# TSL45315-Breakout_v11.net
KiCad netlist of a schematic drawn in EAGLE
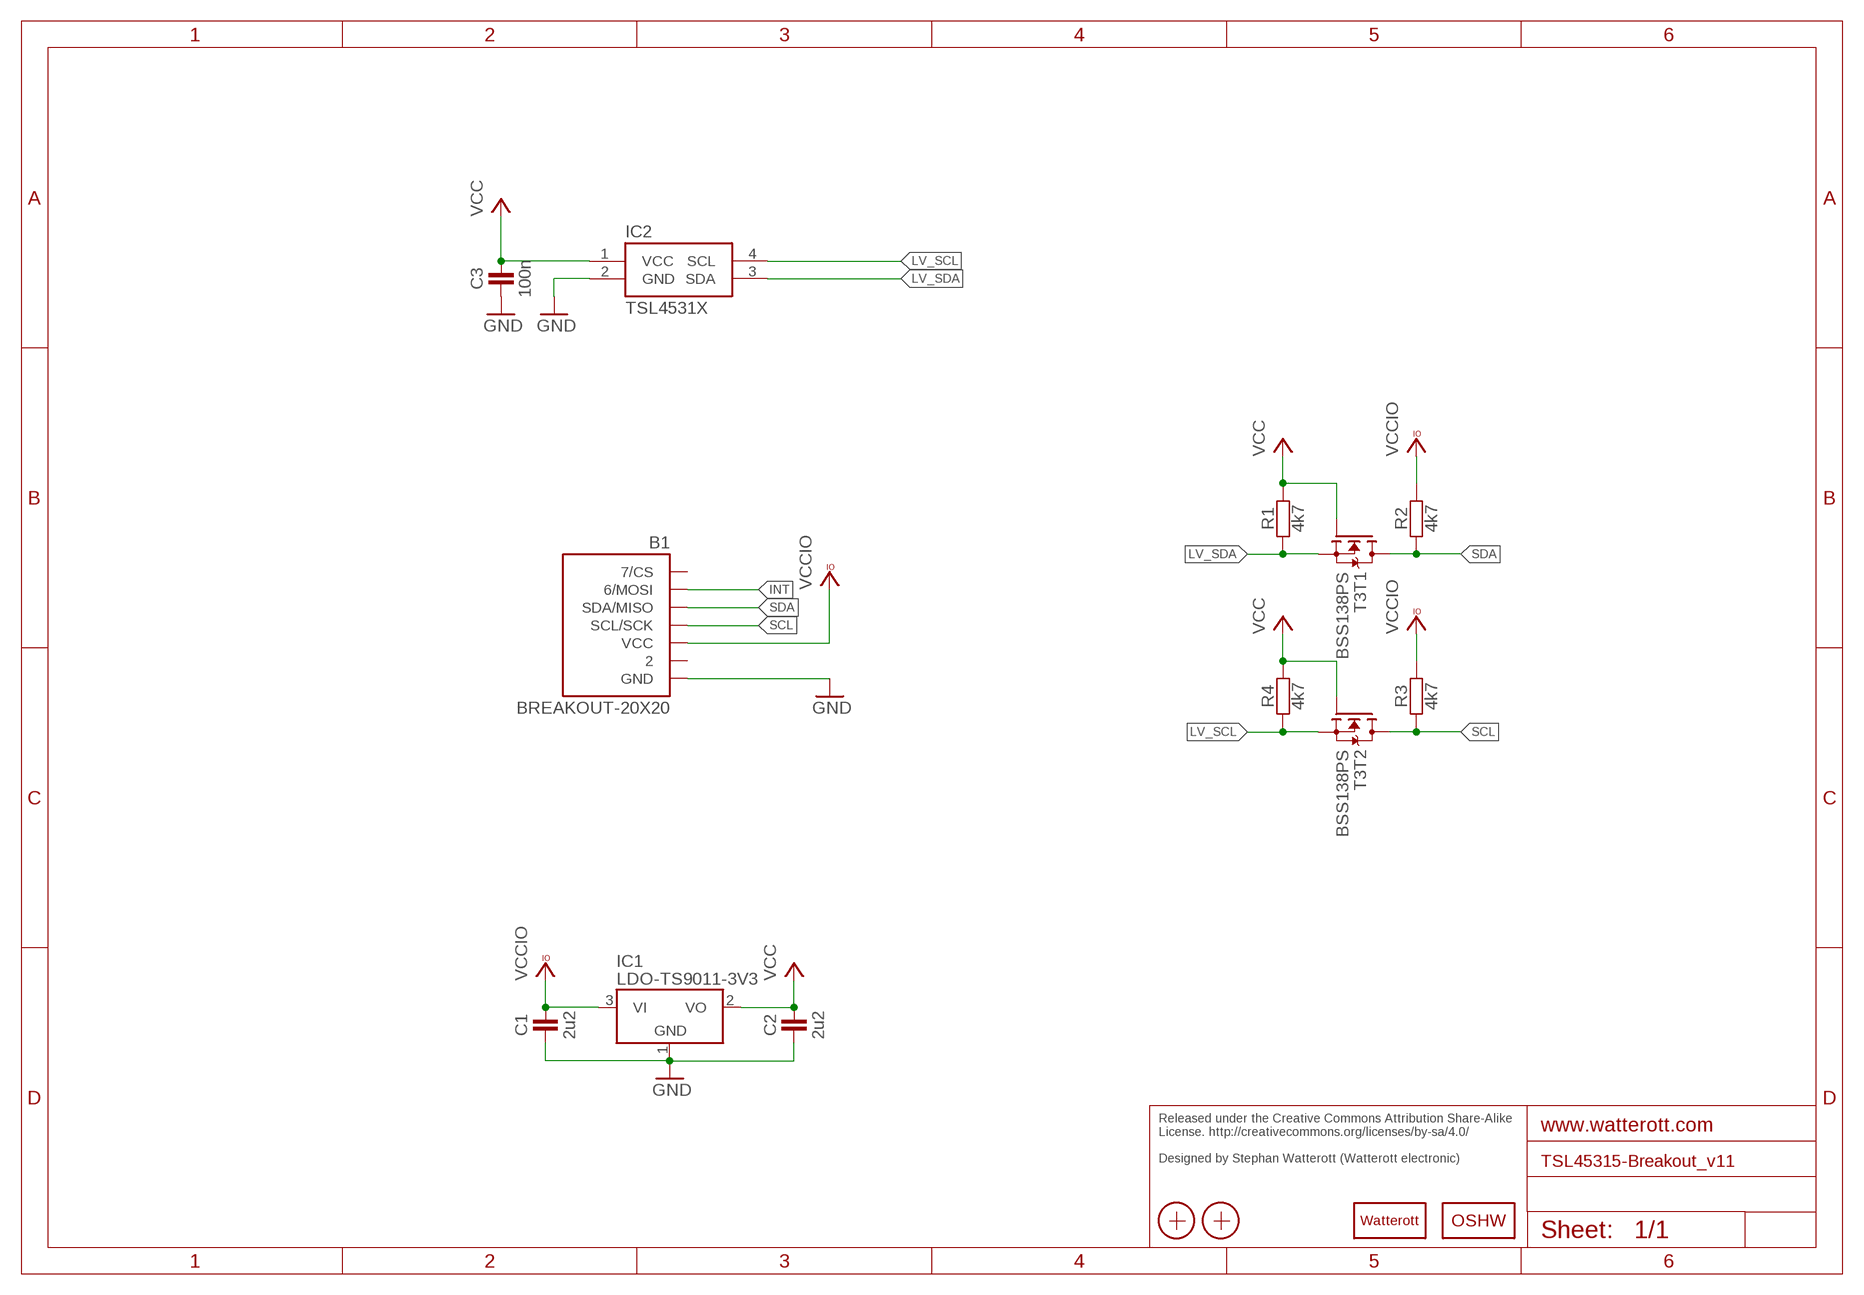
[diagram p0: schematic, sheet 1]

(export (version "E")
  (design (tool "Eeschema 10.0.6"))
  (components
    (comp (ref "B1")
      (value "BREAKOUT-20X20")
      (footprint "eagle-import:BREAKOUT-20X20")
      (libsource (lib "eagle-import") (part "BREAKOUT-20X20"))
    )
    (comp (ref "C1")
      (value "2u2")
      (footprint "eagle-import:C0402")
      (libsource (lib "eagle-import") (part "CAPACITOR-0402"))
    )
    (comp (ref "C2")
      (value "2u2")
      (footprint "eagle-import:C0402")
      (libsource (lib "eagle-import") (part "CAPACITOR-0402"))
    )
    (comp (ref "C3")
      (value "100n")
      (footprint "eagle-import:C0402")
      (libsource (lib "eagle-import") (part "CAPACITOR-0402"))
    )
    (comp (ref "IC1")
      (value "LDO-TS9011-3V3")
      (footprint "eagle-import:SOT23")
      (libsource (lib "eagle-import") (part "LDO-TS9011-3V3"))
    )
    (comp (ref "IC2")
      (value "TSL4531X")
      (footprint "eagle-import:AMS_CL")
      (libsource (lib "eagle-import") (part "TSL4531X"))
    )
    (comp (ref "LOGO1")
      (value "LOGO-S_PLACE_M")
      (footprint "eagle-import:SPARK_TPLACE_M")
      (libsource (lib "eagle-import") (part "LOGO-S_PLACE_M"))
    )
    (comp (ref "LOGO2")
      (value "OSHW_LOGOX0070")
      (footprint "eagle-import:OSHW_6X70")
      (libsource (lib "eagle-import") (part "OSHW_LOGOX0070"))
    )
    (comp (ref "R1")
      (value "4k7")
      (footprint "eagle-import:C0402")
      (libsource (lib "eagle-import") (part "RESISTOR-0402"))
    )
    (comp (ref "R2")
      (value "4k7")
      (footprint "eagle-import:C0402")
      (libsource (lib "eagle-import") (part "RESISTOR-0402"))
    )
    (comp (ref "R3")
      (value "4k7")
      (footprint "eagle-import:C0402")
      (libsource (lib "eagle-import") (part "RESISTOR-0402"))
    )
    (comp (ref "R4")
      (value "4k7")
      (footprint "eagle-import:C0402")
      (libsource (lib "eagle-import") (part "RESISTOR-0402"))
    )
    (comp (ref "T3")
      (value "BSS138PS")
      (footprint "eagle-import:SOT363")
      (libsource (lib "eagle-import") (part "BSS138PS"))
    )
    (comp (ref "X1")
      (value "PASSER-07")
      (footprint "eagle-import:PASSER_07MM")
      (libsource (lib "eagle-import") (part "PASSER-07"))
    )
    (comp (ref "X2")
      (value "PASSER-07")
      (footprint "eagle-import:PASSER_07MM")
      (libsource (lib "eagle-import") (part "PASSER-07"))
    )
  )
  (nets
    (net (code "1") (name "GND") (class "Default")
      (node (ref "B1") (pin "GND") (pinfunction "GND_GND") (pintype "power_in"))
      (node (ref "C1") (pin "1") (pinfunction "1_1") (pintype "passive"))
      (node (ref "C2") (pin "1") (pinfunction "1_1") (pintype "passive"))
      (node (ref "C3") (pin "1") (pinfunction "1_1") (pintype "passive"))
      (node (ref "IC1") (pin "1") (pinfunction "GND_1") (pintype "passive"))
      (node (ref "IC2") (pin "2") (pinfunction "GND_2") (pintype "power_in"))
    )
    (net (code "2") (name "INT") (class "Default")
      (node (ref "B1") (pin "MOSI") (pinfunction "6/MOSI_MOSI") (pintype "bidirectional"))
    )
    (net (code "3") (name "LV_SCL") (class "Default")
      (node (ref "IC2") (pin "4") (pinfunction "SCL_4") (pintype "bidirectional"))
      (node (ref "R4") (pin "1") (pinfunction "1_1") (pintype "passive"))
      (node (ref "T3") (pin "4") (pinfunction "S_4") (pintype "passive"))
    )
    (net (code "4") (name "LV_SDA") (class "Default")
      (node (ref "IC2") (pin "3") (pinfunction "SDA_3") (pintype "bidirectional"))
      (node (ref "R1") (pin "1") (pinfunction "1_1") (pintype "passive"))
      (node (ref "T3") (pin "1") (pinfunction "S_1") (pintype "passive"))
    )
    (net (code "5") (name "SCL") (class "Default")
      (node (ref "B1") (pin "SCL/SCK") (pinfunction "SCL/SCK_SCL/SCK") (pintype "bidirectional"))
      (node (ref "R3") (pin "1") (pinfunction "1_1") (pintype "passive"))
      (node (ref "T3") (pin "3") (pinfunction "D_3") (pintype "passive"))
    )
    (net (code "6") (name "SDA") (class "Default")
      (node (ref "B1") (pin "SDA/MISO") (pinfunction "SDA/MISO_SDA/MISO") (pintype "bidirectional"))
      (node (ref "R2") (pin "1") (pinfunction "1_1") (pintype "passive"))
      (node (ref "T3") (pin "6") (pinfunction "D_6") (pintype "passive"))
    )
    (net (code "7") (name "VCC") (class "Default")
      (node (ref "C2") (pin "2") (pinfunction "2_2") (pintype "passive"))
      (node (ref "C3") (pin "2") (pinfunction "2_2") (pintype "passive"))
      (node (ref "IC1") (pin "2") (pinfunction "VO_2") (pintype "passive"))
      (node (ref "IC2") (pin "1") (pinfunction "VCC_1") (pintype "power_in"))
      (node (ref "R1") (pin "2") (pinfunction "2_2") (pintype "passive"))
      (node (ref "R4") (pin "2") (pinfunction "2_2") (pintype "passive"))
      (node (ref "T3") (pin "2") (pinfunction "G_2") (pintype "passive"))
      (node (ref "T3") (pin "5") (pinfunction "G_5") (pintype "passive"))
    )
    (net (code "8") (name "VCCIO") (class "Default")
      (node (ref "B1") (pin "VCC") (pinfunction "VCC_VCC") (pintype "power_in"))
      (node (ref "C1") (pin "2") (pinfunction "2_2") (pintype "passive"))
      (node (ref "IC1") (pin "3") (pinfunction "VI_3") (pintype "input"))
      (node (ref "R2") (pin "2") (pinfunction "2_2") (pintype "passive"))
      (node (ref "R3") (pin "2") (pinfunction "2_2") (pintype "passive"))
    )
    (net (code "9") (name "unconnected-(B1-7{slash}CS-PadCS)") (class "Default")
      (node (ref "B1") (pin "CS") (pinfunction "7/CS_CS") (pintype "bidirectional"))
    )
    (net (code "10") (name "unconnected-(B1-Pad2)") (class "Default")
      (node (ref "B1") (pin "2") (pinfunction "2_2") (pintype "bidirectional"))
    )
  )
)
